# 01-Antennas.net
KiCad netlist of a schematic drawn in Altium Designer
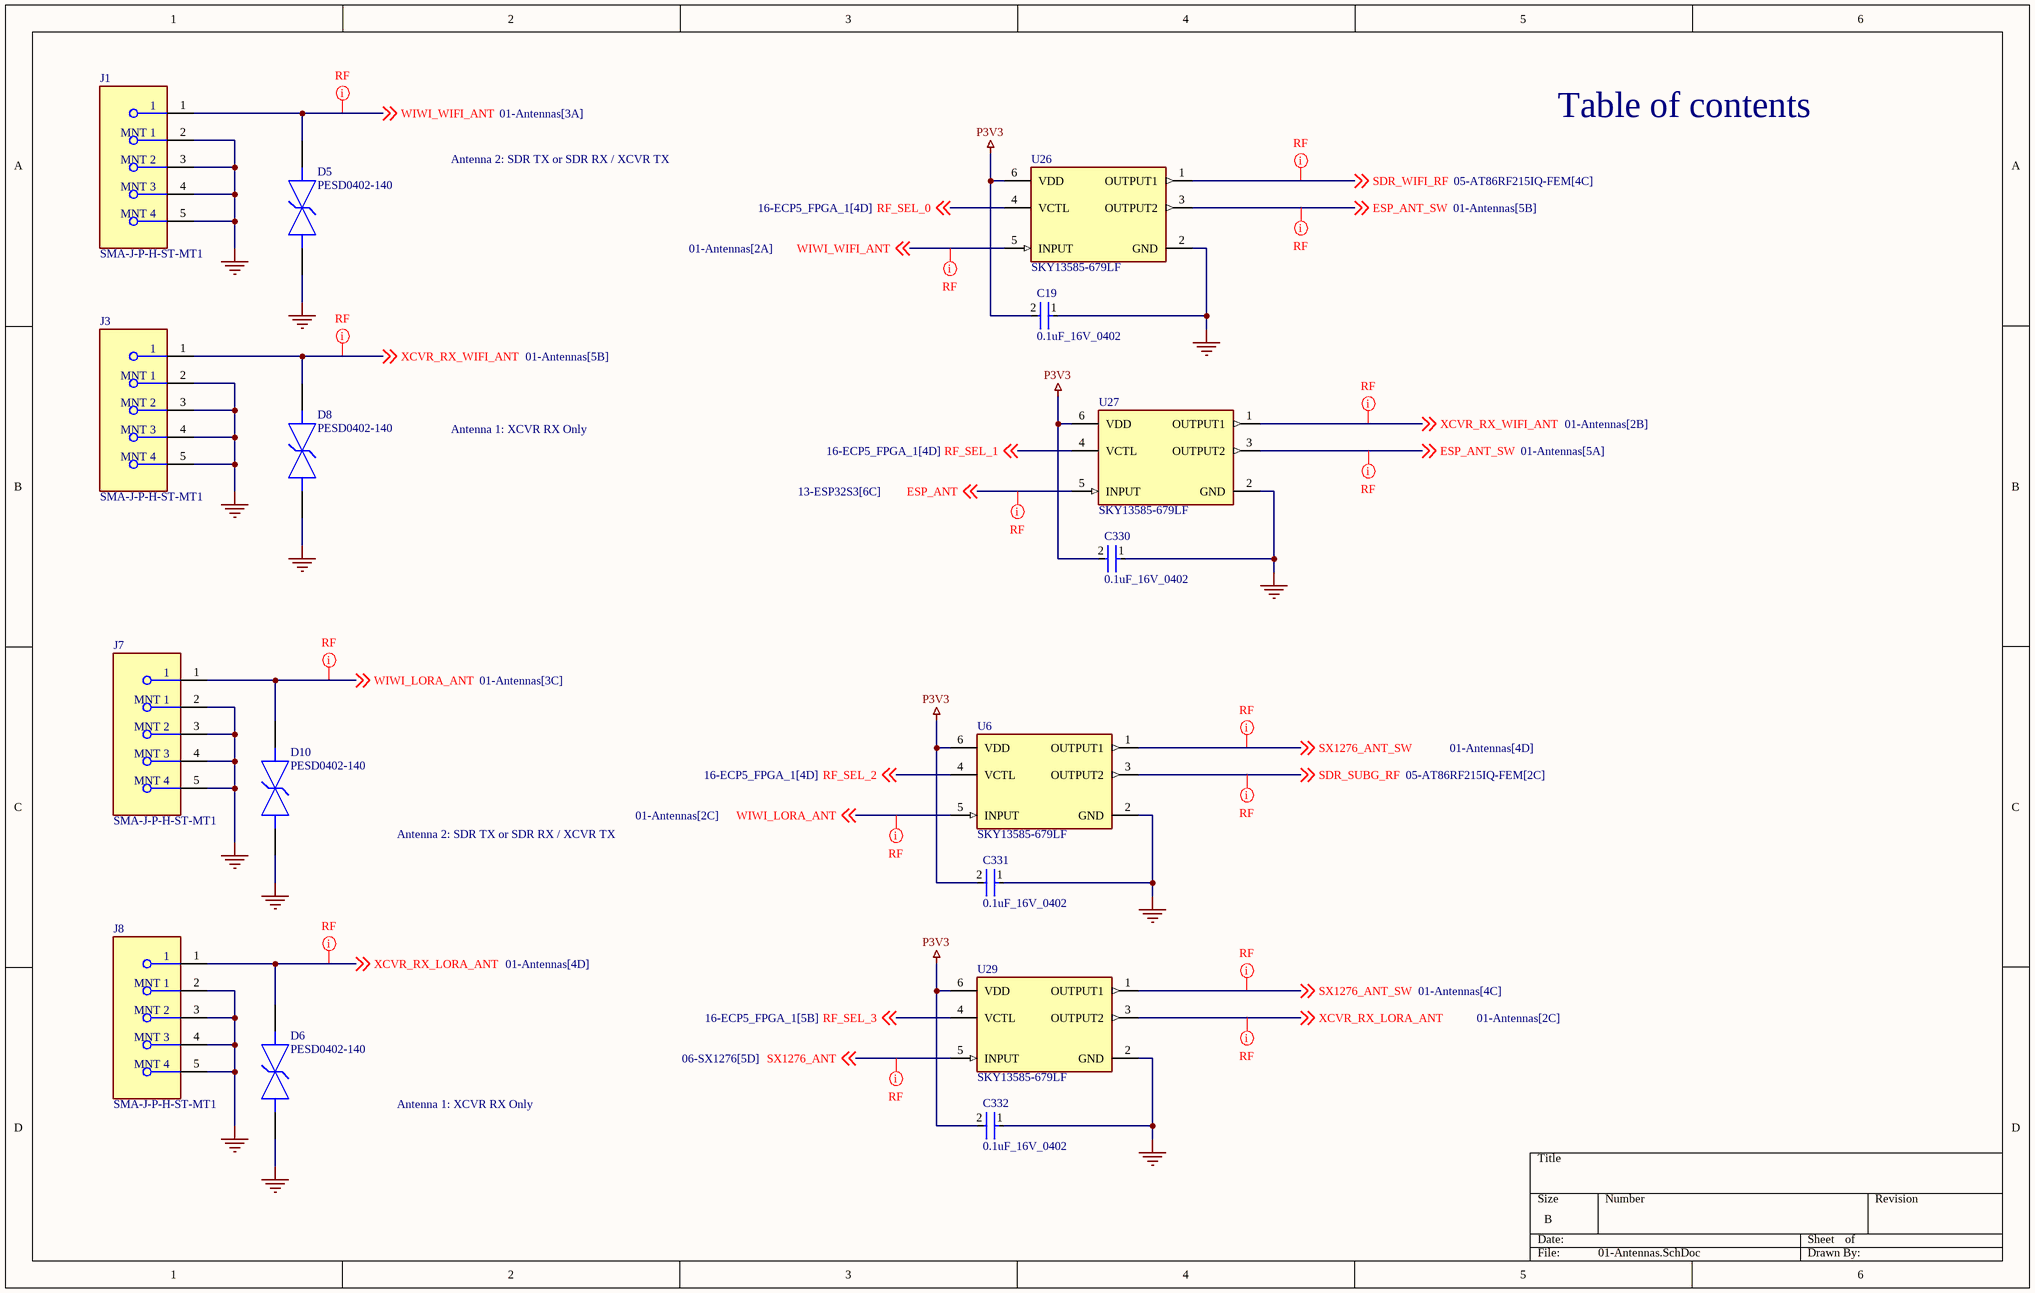
[diagram p0: 01-Antennas.SchDoc]

(export (version "E")
  (design (tool "Eeschema 10.0.6"))
  (components
    (comp (ref "C19")
      (value "0.1uF_16V_0402")
      (footprint "FP-C0402-BB-MFG")
      (description "CAP CER 0.1UF 16V 5% X7R 0402")
      (fields
        (field (name "MANUFACTURER") "Kemet")
        (field (name "MANUFACTURER PART NUMBER") "C0402C104J4RACTU")
      )
      (libsource (lib "Altium Content Vault") (part "b4654b650e69147ec39a6b967a45e02"))
    )
    (comp (ref "C330")
      (value "0.1uF_16V_0402")
      (footprint "FP-C0402-BB-MFG")
      (description "CAP CER 0.1UF 16V 5% X7R 0402")
      (fields
        (field (name "MANUFACTURER") "Kemet")
        (field (name "MANUFACTURER PART NUMBER") "C0402C104J4RACTU")
      )
      (libsource (lib "Altium Content Vault") (part "b4654b650e69147ec39a6b967a45e02"))
    )
    (comp (ref "C331")
      (value "0.1uF_16V_0402")
      (footprint "FP-C0402-BB-MFG")
      (description "CAP CER 0.1UF 16V 5% X7R 0402")
      (fields
        (field (name "MANUFACTURER") "Kemet")
        (field (name "MANUFACTURER PART NUMBER") "C0402C104J4RACTU")
      )
      (libsource (lib "Altium Content Vault") (part "b4654b650e69147ec39a6b967a45e02"))
    )
    (comp (ref "C332")
      (value "0.1uF_16V_0402")
      (footprint "FP-C0402-BB-MFG")
      (description "CAP CER 0.1UF 16V 5% X7R 0402")
      (fields
        (field (name "MANUFACTURER") "Kemet")
        (field (name "MANUFACTURER PART NUMBER") "C0402C104J4RACTU")
      )
      (libsource (lib "Altium Content Vault") (part "b4654b650e69147ec39a6b967a45e02"))
    )
    (comp (ref "D5")
      (value "PESD0402-140")
      (footprint "FP-PESD0402-MFG")
      (description "TVS DIODE 14V 40V 0402")
      (fields
        (field (name "OCTOPART") "https://octopart.com/pesd0402-140-littelfuse-74215061")
        (field (name "MANUFACTURER") "Littelfuse Inc.")
      )
      (libsource (lib "Altium Content Vault") (part "edccc070dd5cba1f9372128faf3915e"))
    )
    (comp (ref "D6")
      (value "PESD0402-140")
      (footprint "FP-PESD0402-MFG")
      (description "TVS DIODE 14V 40V 0402")
      (fields
        (field (name "OCTOPART") "https://octopart.com/pesd0402-140-littelfuse-74215061")
        (field (name "MANUFACTURER") "Littelfuse Inc.")
      )
      (libsource (lib "Altium Content Vault") (part "edccc070dd5cba1f9372128faf3915e"))
    )
    (comp (ref "D8")
      (value "PESD0402-140")
      (footprint "FP-PESD0402-MFG")
      (description "TVS DIODE 14V 40V 0402")
      (fields
        (field (name "OCTOPART") "https://octopart.com/pesd0402-140-littelfuse-74215061")
        (field (name "MANUFACTURER") "Littelfuse Inc.")
      )
      (libsource (lib "Altium Content Vault") (part "edccc070dd5cba1f9372128faf3915e"))
    )
    (comp (ref "D10")
      (value "PESD0402-140")
      (footprint "FP-PESD0402-MFG")
      (description "TVS DIODE 14V 40V 0402")
      (fields
        (field (name "OCTOPART") "https://octopart.com/pesd0402-140-littelfuse-74215061")
        (field (name "MANUFACTURER") "Littelfuse Inc.")
      )
      (libsource (lib "Altium Content Vault") (part "edccc070dd5cba1f9372128faf3915e"))
    )
    (comp (ref "J1")
      (value "SMA-J-P-H-ST-MT1")
      (footprint "FP-SMA-J-P-H-ST-MT1-MFG")
      (description "CONN SMA JACK STR 50 OHM SMD")
      (libsource (lib "Altium Content Vault") (part "9c40ac4d87bbbe9fcb330bd20f98ca3"))
    )
    (comp (ref "J3")
      (value "SMA-J-P-H-ST-MT1")
      (footprint "FP-SMA-J-P-H-ST-MT1-MFG")
      (description "CONN SMA JACK STR 50 OHM SMD")
      (libsource (lib "Altium Content Vault") (part "9c40ac4d87bbbe9fcb330bd20f98ca3"))
    )
    (comp (ref "J7")
      (value "SMA-J-P-H-ST-MT1")
      (footprint "FP-SMA-J-P-H-ST-MT1-MFG")
      (description "CONN SMA JACK STR 50 OHM SMD")
      (libsource (lib "Altium Content Vault") (part "9c40ac4d87bbbe9fcb330bd20f98ca3"))
    )
    (comp (ref "J8")
      (value "SMA-J-P-H-ST-MT1")
      (footprint "FP-SMA-J-P-H-ST-MT1-MFG")
      (description "CONN SMA JACK STR 50 OHM SMD")
      (libsource (lib "Altium Content Vault") (part "9c40ac4d87bbbe9fcb330bd20f98ca3"))
    )
    (comp (ref "U6")
      (value "SKY13585-679LF")
      (footprint "FP-SKY13585-679LF-MFG")
      (description "IC RF SWITCH SPDT 6GHZ 6MLPD")
      (libsource (lib "Altium Content Vault") (part "e67e48af39ab44f3294fce00d3e4f12"))
    )
    (comp (ref "U26")
      (value "SKY13585-679LF")
      (footprint "FP-SKY13585-679LF-MFG")
      (description "IC RF SWITCH SPDT 6GHZ 6MLPD")
      (libsource (lib "Altium Content Vault") (part "e67e48af39ab44f3294fce00d3e4f12"))
    )
    (comp (ref "U27")
      (value "SKY13585-679LF")
      (footprint "FP-SKY13585-679LF-MFG")
      (description "IC RF SWITCH SPDT 6GHZ 6MLPD")
      (libsource (lib "Altium Content Vault") (part "e67e48af39ab44f3294fce00d3e4f12"))
    )
    (comp (ref "U29")
      (value "SKY13585-679LF")
      (footprint "FP-SKY13585-679LF-MFG")
      (description "IC RF SWITCH SPDT 6GHZ 6MLPD")
      (libsource (lib "Altium Content Vault") (part "e67e48af39ab44f3294fce00d3e4f12"))
    )
  )
  (nets
    (net (code "1") (name "ESP_ANT") (class "Default")
      (node (ref "U27") (pin "5") (pinfunction "INPUT_5") (pintype "input"))
    )
    (net (code "2") (name "ESP_ANT_SW") (class "Default")
      (node (ref "U26") (pin "3") (pinfunction "OUTPUT2_3") (pintype "output"))
      (node (ref "U27") (pin "3") (pinfunction "OUTPUT2_3") (pintype "output"))
    )
    (net (code "3") (name "GND") (class "Default")
      (node (ref "C19") (pin "1") (pinfunction "1_1") (pintype "passive"))
      (node (ref "C330") (pin "1") (pinfunction "1_1") (pintype "passive"))
      (node (ref "C331") (pin "1") (pinfunction "1_1") (pintype "passive"))
      (node (ref "C332") (pin "1") (pinfunction "1_1") (pintype "passive"))
      (node (ref "D10") (pin "1") (pinfunction "1_1") (pintype "passive"))
      (node (ref "D5") (pin "1") (pinfunction "1_1") (pintype "passive"))
      (node (ref "D6") (pin "1") (pinfunction "1_1") (pintype "passive"))
      (node (ref "D8") (pin "1") (pinfunction "1_1") (pintype "passive"))
      (node (ref "J1") (pin "2") (pinfunction "MNT_1_2") (pintype "passive"))
      (node (ref "J1") (pin "3") (pinfunction "MNT_2_3") (pintype "passive"))
      (node (ref "J1") (pin "4") (pinfunction "MNT_3_4") (pintype "passive"))
      (node (ref "J1") (pin "5") (pinfunction "MNT_4_5") (pintype "passive"))
      (node (ref "J3") (pin "2") (pinfunction "MNT_1_2") (pintype "passive"))
      (node (ref "J3") (pin "3") (pinfunction "MNT_2_3") (pintype "passive"))
      (node (ref "J3") (pin "4") (pinfunction "MNT_3_4") (pintype "passive"))
      (node (ref "J3") (pin "5") (pinfunction "MNT_4_5") (pintype "passive"))
      (node (ref "J7") (pin "2") (pinfunction "MNT_1_2") (pintype "passive"))
      (node (ref "J7") (pin "3") (pinfunction "MNT_2_3") (pintype "passive"))
      (node (ref "J7") (pin "4") (pinfunction "MNT_3_4") (pintype "passive"))
      (node (ref "J7") (pin "5") (pinfunction "MNT_4_5") (pintype "passive"))
      (node (ref "J8") (pin "2") (pinfunction "MNT_1_2") (pintype "passive"))
      (node (ref "J8") (pin "3") (pinfunction "MNT_2_3") (pintype "passive"))
      (node (ref "J8") (pin "4") (pinfunction "MNT_3_4") (pintype "passive"))
      (node (ref "J8") (pin "5") (pinfunction "MNT_4_5") (pintype "passive"))
      (node (ref "U26") (pin "2") (pinfunction "GND_2") (pintype "power_in"))
      (node (ref "U27") (pin "2") (pinfunction "GND_2") (pintype "power_in"))
      (node (ref "U29") (pin "2") (pinfunction "GND_2") (pintype "power_in"))
      (node (ref "U6") (pin "2") (pinfunction "GND_2") (pintype "power_in"))
    )
    (net (code "4") (name "P3V3") (class "Default")
      (node (ref "C19") (pin "2") (pinfunction "2_2") (pintype "passive"))
      (node (ref "C330") (pin "2") (pinfunction "2_2") (pintype "passive"))
      (node (ref "C331") (pin "2") (pinfunction "2_2") (pintype "passive"))
      (node (ref "C332") (pin "2") (pinfunction "2_2") (pintype "passive"))
      (node (ref "U26") (pin "6") (pinfunction "VDD_6") (pintype "power_in"))
      (node (ref "U27") (pin "6") (pinfunction "VDD_6") (pintype "power_in"))
      (node (ref "U29") (pin "6") (pinfunction "VDD_6") (pintype "power_in"))
      (node (ref "U6") (pin "6") (pinfunction "VDD_6") (pintype "power_in"))
    )
    (net (code "5") (name "RF_SEL_0") (class "Default")
      (node (ref "U26") (pin "4") (pinfunction "VCTL_4") (pintype "power_in"))
    )
    (net (code "6") (name "RF_SEL_1") (class "Default")
      (node (ref "U27") (pin "4") (pinfunction "VCTL_4") (pintype "power_in"))
    )
    (net (code "7") (name "RF_SEL_2") (class "Default")
      (node (ref "U6") (pin "4") (pinfunction "VCTL_4") (pintype "power_in"))
    )
    (net (code "8") (name "RF_SEL_3") (class "Default")
      (node (ref "U29") (pin "4") (pinfunction "VCTL_4") (pintype "power_in"))
    )
    (net (code "9") (name "SDR_SUBG_RF") (class "Default")
      (node (ref "U6") (pin "3") (pinfunction "OUTPUT2_3") (pintype "output"))
    )
    (net (code "10") (name "SDR_WIFI_RF") (class "Default")
      (node (ref "U26") (pin "1") (pinfunction "OUTPUT1_1") (pintype "output"))
    )
    (net (code "11") (name "SX1276_ANT") (class "Default")
      (node (ref "U29") (pin "5") (pinfunction "INPUT_5") (pintype "input"))
    )
    (net (code "12") (name "SX1276_ANT_SW") (class "Default")
      (node (ref "U29") (pin "1") (pinfunction "OUTPUT1_1") (pintype "output"))
      (node (ref "U6") (pin "1") (pinfunction "OUTPUT1_1") (pintype "output"))
    )
    (net (code "13") (name "WIWI_LORA_ANT") (class "Default")
      (node (ref "D10") (pin "2") (pinfunction "2_2") (pintype "passive"))
      (node (ref "J7") (pin "1") (pinfunction "1_1") (pintype "passive"))
      (node (ref "U6") (pin "5") (pinfunction "INPUT_5") (pintype "input"))
    )
    (net (code "14") (name "WIWI_WIFI_ANT") (class "Default")
      (node (ref "D5") (pin "2") (pinfunction "2_2") (pintype "passive"))
      (node (ref "J1") (pin "1") (pinfunction "1_1") (pintype "passive"))
      (node (ref "U26") (pin "5") (pinfunction "INPUT_5") (pintype "input"))
    )
    (net (code "15") (name "XCVR_RX_LORA_ANT") (class "Default")
      (node (ref "D6") (pin "2") (pinfunction "2_2") (pintype "passive"))
      (node (ref "J8") (pin "1") (pinfunction "1_1") (pintype "passive"))
      (node (ref "U29") (pin "3") (pinfunction "OUTPUT2_3") (pintype "output"))
    )
    (net (code "16") (name "XCVR_RX_WIFI_ANT") (class "Default")
      (node (ref "D8") (pin "2") (pinfunction "2_2") (pintype "passive"))
      (node (ref "J3") (pin "1") (pinfunction "1_1") (pintype "passive"))
      (node (ref "U27") (pin "1") (pinfunction "OUTPUT1_1") (pintype "output"))
    )
  )
)
